# temperatureSensor.net
KiCad netlist of a schematic drawn in EAGLE
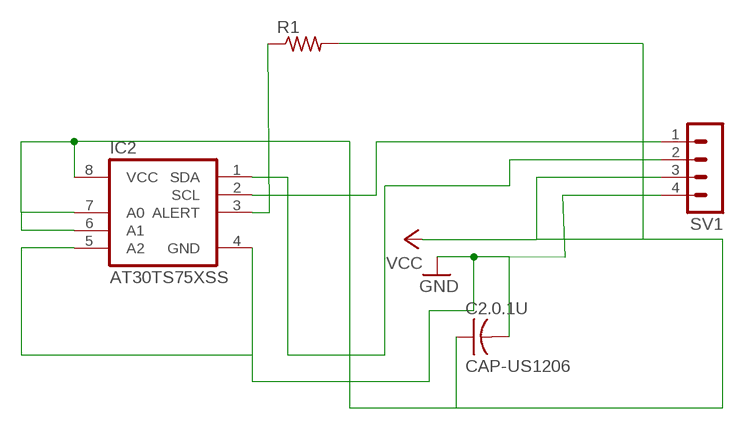
[diagram p0: schematic, sheet 1]

(export (version "E")
  (design (tool "Eeschema 10.0.6"))
  (components
    (comp (ref "C2.0.1U")
      (value "CAP-US1206")
      (footprint "eagle-import:C1206")
      (libsource (lib "eagle-import") (part "CAP-US1206"))
    )
    (comp (ref "IC2")
      (value "AT30TS75XSS")
      (footprint "eagle-import:SO8")
      (libsource (lib "eagle-import") (part "AT30TS75XSS"))
    )
    (comp (ref "R1")
      (value "RES-US1206")
      (footprint "eagle-import:R1206")
      (libsource (lib "eagle-import") (part "RES-US1206"))
    )
    (comp (ref "SV1")
      (value "MA04-1")
      (footprint "eagle-import:MA04-1")
      (libsource (lib "eagle-import") (part "MA04-1"))
    )
  )
  (nets
    (net (code "1") (name "GND") (class "Default")
      (node (ref "C2.0.1U") (pin "2") (pinfunction "2_2") (pintype "passive"))
      (node (ref "IC2") (pin "4") (pinfunction "GND_4") (pintype "power_in"))
      (node (ref "IC2") (pin "5") (pinfunction "A2_5") (pintype "input"))
      (node (ref "SV1") (pin "4") (pinfunction "4_4") (pintype "passive"))
    )
    (net (code "2") (name "Net-(IC2-ALERT)") (class "Default")
      (node (ref "IC2") (pin "3") (pinfunction "ALERT_3") (pintype "output"))
      (node (ref "R1") (pin "1") (pinfunction "1_1") (pintype "passive"))
    )
    (net (code "3") (name "Net-(IC2-SCL)") (class "Default")
      (node (ref "IC2") (pin "2") (pinfunction "SCL_2") (pintype "input"))
      (node (ref "SV1") (pin "1") (pinfunction "1_1") (pintype "passive"))
    )
    (net (code "4") (name "Net-(IC2-SDA)") (class "Default")
      (node (ref "IC2") (pin "1") (pinfunction "SDA_1") (pintype "bidirectional"))
      (node (ref "SV1") (pin "2") (pinfunction "2_2") (pintype "passive"))
    )
    (net (code "5") (name "VCC") (class "Default")
      (node (ref "C2.0.1U") (pin "1") (pinfunction "1_1") (pintype "passive"))
      (node (ref "IC2") (pin "6") (pinfunction "A1_6") (pintype "input"))
      (node (ref "IC2") (pin "7") (pinfunction "A0_7") (pintype "input"))
      (node (ref "IC2") (pin "8") (pinfunction "VCC_8") (pintype "power_in"))
      (node (ref "R1") (pin "2") (pinfunction "2_2") (pintype "passive"))
      (node (ref "SV1") (pin "3") (pinfunction "3_3") (pintype "passive"))
    )
  )
)
